# lp_pic32.net
KiCad netlist of a schematic drawn in EAGLE
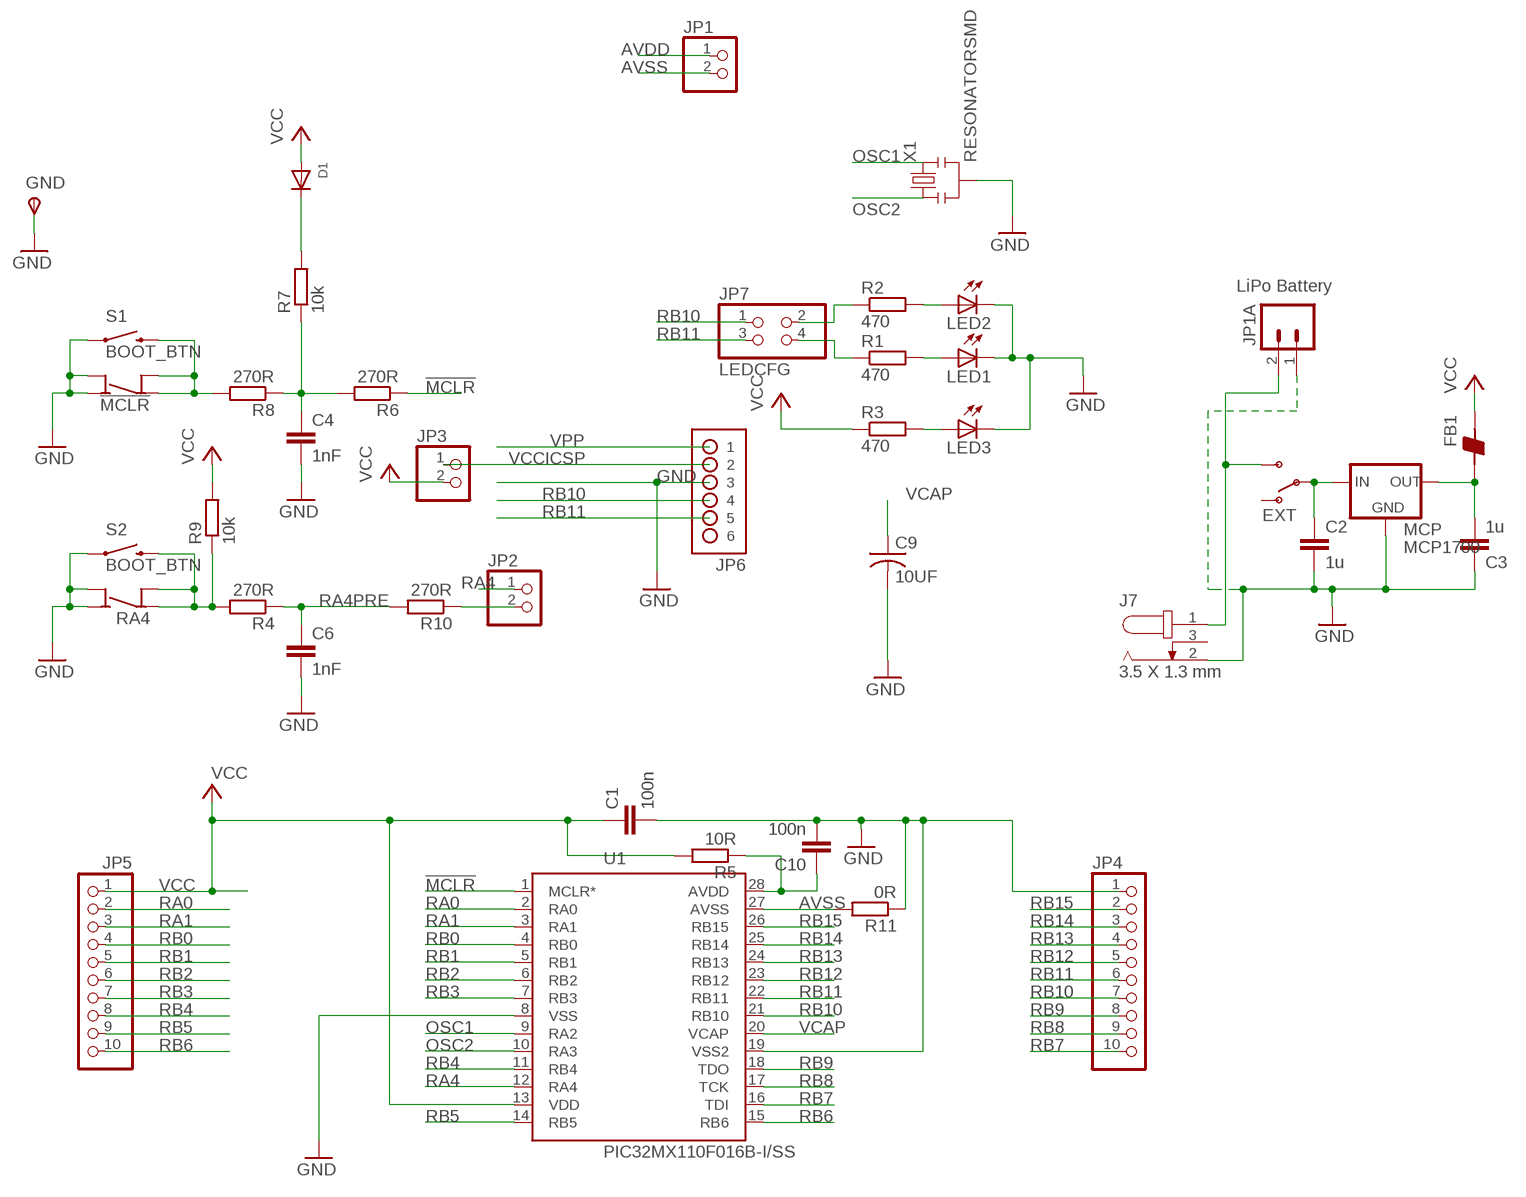
[diagram p0: schematic, sheet 1]

(export (version "E")
  (design (tool "Eeschema 10.0.6"))
  (components
    (comp (ref "!MCLR")
      (value "!MCLR")
      (footprint "eagle-import:6MMTACTILE_4PIN")
      (libsource (lib "eagle-import") (part "SPST4"))
    )
    (comp (ref "C1")
      (value "100n")
      (footprint "eagle-import:C0805")
      (libsource (lib "eagle-import") (part "C-EUC0805"))
    )
    (comp (ref "C2")
      (value "1u")
      (footprint "eagle-import:C0805")
      (libsource (lib "eagle-import") (part "C-EUC0805"))
    )
    (comp (ref "C3")
      (value "1u")
      (footprint "eagle-import:C0805")
      (libsource (lib "eagle-import") (part "C-EUC0805"))
    )
    (comp (ref "C4")
      (value "1nF")
      (footprint "eagle-import:C0805")
      (libsource (lib "eagle-import") (part "resistor_C-EUC0805"))
    )
    (comp (ref "C6")
      (value "1nF")
      (footprint "eagle-import:C0805")
      (libsource (lib "eagle-import") (part "resistor_C-EUC0805"))
    )
    (comp (ref "C9")
      (value "10UF")
      (footprint "eagle-import:C1206")
      (libsource (lib "eagle-import") (part "C-USC1206"))
    )
    (comp (ref "C10")
      (value "100n")
      (footprint "eagle-import:C0805")
      (libsource (lib "eagle-import") (part "C-EUC0805"))
    )
    (comp (ref "D1")
      (value "DIODESOD-323F")
      (footprint "eagle-import:SOD-323F")
      (libsource (lib "eagle-import") (part "DIODESOD-323F"))
    )
    (comp (ref "FB1")
      (value "BEAD-0805")
      (footprint "eagle-import:0805")
      (libsource (lib "eagle-import") (part "BEAD-0805"))
    )
    (comp (ref "GND")
      (value "TPSTP20R")
      (footprint "eagle-import:TP20R")
      (libsource (lib "eagle-import") (part "TPSTP20R"))
    )
    (comp (ref "J7")
      (value "3.5 X 1.3 mm")
      (footprint "eagle-import:3.5X1.3MM_DC_JACK")
      (libsource (lib "eagle-import") (part "DC_JACK_3.5X1.3MM"))
    )
    (comp (ref "JP1")
      (value "PINHD-1X2")
      (footprint "eagle-import:1X02")
      (libsource (lib "eagle-import") (part "PINHD-1X2"))
    )
    (comp (ref "JP1A")
      (value "LiPo Battery")
      (footprint "eagle-import:JST-2-PTH")
      (libsource (lib "eagle-import") (part "M02JST-PTH-2"))
    )
    (comp (ref "JP2")
      (value "PINHD-1X2")
      (footprint "eagle-import:1X02")
      (libsource (lib "eagle-import") (part "PINHD-1X2"))
    )
    (comp (ref "JP3")
      (value "PINHD-1X2")
      (footprint "eagle-import:1X02")
      (libsource (lib "eagle-import") (part "PINHD-1X2"))
    )
    (comp (ref "JP4")
      (value "PH1X10OCT076")
      (footprint "eagle-import:PH1X10OCT76")
      (libsource (lib "eagle-import") (part "PH1X10OCT076"))
    )
    (comp (ref "JP5")
      (value "PH1X10OCT076")
      (footprint "eagle-import:PH1X10OCT76")
      (libsource (lib "eagle-import") (part "PH1X10OCT076"))
    )
    (comp (ref "JP6")
      (value "No Load")
      (footprint "eagle-import:HDR-1X6_OFFSET")
      (libsource (lib "eagle-import") (part "HDR-1X6-OFFSET"))
    )
    (comp (ref "JP7")
      (value "LEDCFG")
      (footprint "eagle-import:2X02")
      (libsource (lib "eagle-import") (part "PINHD-2X2"))
    )
    (comp (ref "LED1")
      (value "0")
      (footprint "eagle-import:CHIPLED_1206")
      (libsource (lib "eagle-import") (part "LEDCHIPLED_1206"))
    )
    (comp (ref "LED2")
      (value "0")
      (footprint "eagle-import:CHIPLED_1206")
      (libsource (lib "eagle-import") (part "LEDCHIPLED_1206"))
    )
    (comp (ref "LED3")
      (value "0")
      (footprint "eagle-import:CHIPLED_1206")
      (libsource (lib "eagle-import") (part "LEDCHIPLED_1206"))
    )
    (comp (ref "MCP")
      (value "MCP1700")
      (footprint "eagle-import:SOT-23")
      (libsource (lib "eagle-import") (part "MCP1700SOT-23"))
    )
    (comp (ref "ON")
      (value "EXT")
      (footprint "eagle-import:SWITCH-SPDT")
      (libsource (lib "eagle-import") (part "SWITCH-SPSTPTH"))
    )
    (comp (ref "R1")
      (value "470")
      (footprint "eagle-import:R0805")
      (libsource (lib "eagle-import") (part "R-EU_R0805"))
    )
    (comp (ref "R2")
      (value "470")
      (footprint "eagle-import:R0805")
      (libsource (lib "eagle-import") (part "R-EU_R0805"))
    )
    (comp (ref "R3")
      (value "470")
      (footprint "eagle-import:R0805")
      (libsource (lib "eagle-import") (part "R-EU_R0805"))
    )
    (comp (ref "R4")
      (value "270R")
      (footprint "eagle-import:R0805")
      (libsource (lib "eagle-import") (part "R-EU_R0805"))
    )
    (comp (ref "R5")
      (value "10R")
      (footprint "eagle-import:R0805")
      (libsource (lib "eagle-import") (part "R-EU_R0805"))
    )
    (comp (ref "R6")
      (value "270R")
      (footprint "eagle-import:R0805")
      (libsource (lib "eagle-import") (part "R-EU_R0805"))
    )
    (comp (ref "R7")
      (value "10k")
      (footprint "eagle-import:R0805")
      (libsource (lib "eagle-import") (part "R-EU_R0805"))
    )
    (comp (ref "R8")
      (value "270R")
      (footprint "eagle-import:R0805")
      (libsource (lib "eagle-import") (part "R-EU_R0805"))
    )
    (comp (ref "R9")
      (value "10k")
      (footprint "eagle-import:R0805")
      (libsource (lib "eagle-import") (part "R-EU_R0805"))
    )
    (comp (ref "R10")
      (value "270R")
      (footprint "eagle-import:R0805")
      (libsource (lib "eagle-import") (part "R-EU_R0805"))
    )
    (comp (ref "R11")
      (value "0R")
      (footprint "eagle-import:R0805")
      (libsource (lib "eagle-import") (part "R-EU_R0805"))
    )
    (comp (ref "RA4")
      (value "RA4")
      (footprint "eagle-import:6MMTACTILE_4PIN")
      (libsource (lib "eagle-import") (part "SPST4"))
    )
    (comp (ref "S1")
      (value "BOOT_BTN")
      (footprint "eagle-import:TACTILE-SWITCH-1101NE")
      (libsource (lib "eagle-import") (part "SWITCH-MOMENTARY-2-SMD-1101NE"))
    )
    (comp (ref "S2")
      (value "BOOT_BTN")
      (footprint "eagle-import:TACTILE-SWITCH-1101NE")
      (libsource (lib "eagle-import") (part "SWITCH-MOMENTARY-2-SMD-1101NE"))
    )
    (comp (ref "U1")
      (value "PIC32MX110F016B-I/SS")
      (footprint "eagle-import:SOP65P780X200-28N")
      (libsource (lib "eagle-import") (part "PIC32MX/SS110F016B-I"))
    )
    (comp (ref "X1")
      (value "RESONATORSMD")
      (footprint "eagle-import:RESONATOR-SMD")
      (libsource (lib "eagle-import") (part "RESONATORSMD"))
    )
  )
  (nets
    (net (code "1") (name "/AVDD") (class "Default")
      (node (ref "C10") (pin "1") (pinfunction "1_1") (pintype "passive"))
      (node (ref "JP1") (pin "1") (pinfunction "1_1") (pintype "passive"))
      (node (ref "R5") (pin "1") (pinfunction "1_1") (pintype "passive"))
      (node (ref "U1") (pin "28") (pinfunction "AVDD_28") (pintype "power_in"))
    )
    (net (code "2") (name "/AVSS") (class "Default")
      (node (ref "JP1") (pin "2") (pinfunction "2_2") (pintype "passive"))
      (node (ref "R11") (pin "2") (pinfunction "2_2") (pintype "passive"))
      (node (ref "U1") (pin "27") (pinfunction "AVSS_27") (pintype "power_in"))
    )
    (net (code "3") (name "/OSC1") (class "Default")
      (node (ref "U1") (pin "9") (pinfunction "RA2_9") (pintype "bidirectional"))
      (node (ref "X1") (pin "3") (pinfunction "3_3") (pintype "passive"))
    )
    (net (code "4") (name "/OSC2") (class "Default")
      (node (ref "U1") (pin "10") (pinfunction "RA3_10") (pintype "bidirectional"))
      (node (ref "X1") (pin "1") (pinfunction "1_1") (pintype "passive"))
    )
    (net (code "5") (name "/RA0") (class "Default")
      (node (ref "JP5") (pin "2") (pinfunction "2_2") (pintype "passive"))
      (node (ref "U1") (pin "2") (pinfunction "RA0_2") (pintype "bidirectional"))
    )
    (net (code "6") (name "/RA1") (class "Default")
      (node (ref "JP5") (pin "3") (pinfunction "3_3") (pintype "passive"))
      (node (ref "U1") (pin "3") (pinfunction "RA1_3") (pintype "bidirectional"))
    )
    (net (code "7") (name "/RA4") (class "Default")
      (node (ref "JP2") (pin "1") (pinfunction "1_1") (pintype "passive"))
      (node (ref "U1") (pin "12") (pinfunction "RA4_12") (pintype "bidirectional"))
    )
    (net (code "8") (name "/RA4PRE") (class "Default")
      (node (ref "C6") (pin "1") (pinfunction "1_1") (pintype "passive"))
      (node (ref "R10") (pin "2") (pinfunction "2_2") (pintype "passive"))
      (node (ref "R4") (pin "1") (pinfunction "1_1") (pintype "passive"))
    )
    (net (code "9") (name "/RB0") (class "Default")
      (node (ref "JP5") (pin "4") (pinfunction "4_4") (pintype "passive"))
      (node (ref "U1") (pin "4") (pinfunction "RB0_4") (pintype "bidirectional"))
    )
    (net (code "10") (name "/RB1") (class "Default")
      (node (ref "JP5") (pin "5") (pinfunction "5_5") (pintype "passive"))
      (node (ref "U1") (pin "5") (pinfunction "RB1_5") (pintype "bidirectional"))
    )
    (net (code "11") (name "/RB2") (class "Default")
      (node (ref "JP5") (pin "6") (pinfunction "6_6") (pintype "passive"))
      (node (ref "U1") (pin "6") (pinfunction "RB2_6") (pintype "bidirectional"))
    )
    (net (code "12") (name "/RB3") (class "Default")
      (node (ref "JP5") (pin "7") (pinfunction "7_7") (pintype "passive"))
      (node (ref "U1") (pin "7") (pinfunction "RB3_7") (pintype "bidirectional"))
    )
    (net (code "13") (name "/RB4") (class "Default")
      (node (ref "JP5") (pin "8") (pinfunction "8_8") (pintype "passive"))
      (node (ref "U1") (pin "11") (pinfunction "RB4_11") (pintype "bidirectional"))
    )
    (net (code "14") (name "/RB5") (class "Default")
      (node (ref "JP5") (pin "9") (pinfunction "9_9") (pintype "passive"))
      (node (ref "U1") (pin "14") (pinfunction "RB5_14") (pintype "bidirectional"))
    )
    (net (code "15") (name "/RB6") (class "Default")
      (node (ref "JP5") (pin "10") (pinfunction "10_10") (pintype "passive"))
      (node (ref "U1") (pin "15") (pinfunction "RB6_15") (pintype "bidirectional"))
    )
    (net (code "16") (name "/RB7") (class "Default")
      (node (ref "JP4") (pin "10") (pinfunction "10_10") (pintype "passive"))
      (node (ref "U1") (pin "16") (pinfunction "TDI_16") (pintype "input"))
    )
    (net (code "17") (name "/RB8") (class "Default")
      (node (ref "JP4") (pin "9") (pinfunction "9_9") (pintype "passive"))
      (node (ref "U1") (pin "17") (pinfunction "TCK_17") (pintype "input"))
    )
    (net (code "18") (name "/RB9") (class "Default")
      (node (ref "JP4") (pin "8") (pinfunction "8_8") (pintype "passive"))
      (node (ref "U1") (pin "18") (pinfunction "TDO_18") (pintype "output"))
    )
    (net (code "19") (name "/RB10") (class "Default")
      (node (ref "JP4") (pin "7") (pinfunction "7_7") (pintype "passive"))
      (node (ref "JP6") (pin "4") (pinfunction "4_4") (pintype "passive"))
      (node (ref "JP7") (pin "1") (pinfunction "1_1") (pintype "passive"))
      (node (ref "U1") (pin "21") (pinfunction "RB10_21") (pintype "bidirectional"))
    )
    (net (code "20") (name "/RB11") (class "Default")
      (node (ref "JP4") (pin "6") (pinfunction "6_6") (pintype "passive"))
      (node (ref "JP6") (pin "5") (pinfunction "5_5") (pintype "passive"))
      (node (ref "JP7") (pin "3") (pinfunction "3_3") (pintype "passive"))
      (node (ref "U1") (pin "22") (pinfunction "RB11_22") (pintype "bidirectional"))
    )
    (net (code "21") (name "/RB12") (class "Default")
      (node (ref "JP4") (pin "5") (pinfunction "5_5") (pintype "passive"))
      (node (ref "U1") (pin "23") (pinfunction "RB12_23") (pintype "bidirectional"))
    )
    (net (code "22") (name "/RB13") (class "Default")
      (node (ref "JP4") (pin "4") (pinfunction "4_4") (pintype "passive"))
      (node (ref "U1") (pin "24") (pinfunction "RB13_24") (pintype "bidirectional"))
    )
    (net (code "23") (name "/RB14") (class "Default")
      (node (ref "JP4") (pin "3") (pinfunction "3_3") (pintype "passive"))
      (node (ref "U1") (pin "25") (pinfunction "RB14_25") (pintype "bidirectional"))
    )
    (net (code "24") (name "/RB15") (class "Default")
      (node (ref "JP4") (pin "2") (pinfunction "2_2") (pintype "passive"))
      (node (ref "U1") (pin "26") (pinfunction "RB15_26") (pintype "bidirectional"))
    )
    (net (code "25") (name "/VCAP") (class "Default")
      (node (ref "C9") (pin "1") (pinfunction "1_1") (pintype "passive"))
      (node (ref "U1") (pin "20") (pinfunction "VCAP_20") (pintype "power_in"))
    )
    (net (code "26") (name "/VCCICSP") (class "Default")
      (node (ref "JP3") (pin "1") (pinfunction "1_1") (pintype "passive"))
      (node (ref "JP6") (pin "2") (pinfunction "2_2") (pintype "passive"))
    )
    (net (code "27") (name "/VPP") (class "Default")
      (node (ref "C4") (pin "1") (pinfunction "1_1") (pintype "passive"))
      (node (ref "JP6") (pin "1") (pinfunction "1_1") (pintype "passive"))
      (node (ref "R6") (pin "2") (pinfunction "2_2") (pintype "passive"))
      (node (ref "R7") (pin "1") (pinfunction "1_1") (pintype "passive"))
      (node (ref "R8") (pin "1") (pinfunction "1_1") (pintype "passive"))
    )
    (net (code "28") (name "/~{MCLR}") (class "Default")
      (node (ref "R6") (pin "1") (pinfunction "1_1") (pintype "passive"))
      (node (ref "U1") (pin "1") (pinfunction "MCLR*_1") (pintype "input"))
    )
    (net (code "29") (name "GND") (class "Default")
      (node (ref "!MCLR") (pin "A1") (pinfunction "NO_A1") (pintype "passive"))
      (node (ref "!MCLR") (pin "A2") (pinfunction "NO_A2") (pintype "passive"))
      (node (ref "C1") (pin "2") (pinfunction "2_2") (pintype "passive"))
      (node (ref "C10") (pin "2") (pinfunction "2_2") (pintype "passive"))
      (node (ref "C2") (pin "2") (pinfunction "2_2") (pintype "passive"))
      (node (ref "C3") (pin "1") (pinfunction "1_1") (pintype "passive"))
      (node (ref "C4") (pin "2") (pinfunction "2_2") (pintype "passive"))
      (node (ref "C6") (pin "2") (pinfunction "2_2") (pintype "passive"))
      (node (ref "C9") (pin "2") (pinfunction "2_2") (pintype "passive"))
      (node (ref "GND") (pin "TP") (pinfunction "PP_TP") (pintype "input"))
      (node (ref "J7") (pin "2") (pinfunction "2_2") (pintype "passive"))
      (node (ref "JP1A") (pin "1") (pinfunction "1_1") (pintype "passive"))
      (node (ref "JP4") (pin "1") (pinfunction "1_1") (pintype "passive"))
      (node (ref "JP6") (pin "3") (pinfunction "3_3") (pintype "passive"))
      (node (ref "LED1") (pin "C") (pinfunction "C_C") (pintype "passive"))
      (node (ref "LED2") (pin "C") (pinfunction "C_C") (pintype "passive"))
      (node (ref "LED3") (pin "C") (pinfunction "C_C") (pintype "passive"))
      (node (ref "MCP") (pin "1") (pinfunction "GND_1") (pintype "input"))
      (node (ref "R11") (pin "1") (pinfunction "1_1") (pintype "passive"))
      (node (ref "RA4") (pin "A1") (pinfunction "NO_A1") (pintype "passive"))
      (node (ref "RA4") (pin "A2") (pinfunction "NO_A2") (pintype "passive"))
      (node (ref "S1") (pin "1") (pinfunction "1_1") (pintype "passive"))
      (node (ref "S2") (pin "1") (pinfunction "1_1") (pintype "passive"))
      (node (ref "U1") (pin "19") (pinfunction "VSS2_19") (pintype "power_in"))
      (node (ref "U1") (pin "8") (pinfunction "VSS_8") (pintype "power_in"))
      (node (ref "X1") (pin "2") (pinfunction "2_2") (pintype "passive"))
    )
    (net (code "30") (name "Net-(!MCLR-COM-PadB1)") (class "Default")
      (node (ref "!MCLR") (pin "B1") (pinfunction "COM_B1") (pintype "passive"))
      (node (ref "!MCLR") (pin "B2") (pinfunction "COM_B2") (pintype "passive"))
      (node (ref "R8") (pin "2") (pinfunction "2_2") (pintype "passive"))
      (node (ref "S1") (pin "2") (pinfunction "2_2") (pintype "passive"))
    )
    (net (code "31") (name "Net-(D1-PadC)") (class "Default")
      (node (ref "D1") (pin "C") (pinfunction "C_C") (pintype "passive"))
      (node (ref "R7") (pin "2") (pinfunction "2_2") (pintype "passive"))
    )
    (net (code "32") (name "Net-(FB1-P$1)") (class "Default")
      (node (ref "C3") (pin "2") (pinfunction "2_2") (pintype "passive"))
      (node (ref "FB1") (pin "1") (pinfunction "P$1_1") (pintype "passive"))
      (node (ref "MCP") (pin "2") (pinfunction "OUT_2") (pintype "passive"))
    )
    (net (code "33") (name "Net-(JP2-Pad2)") (class "Default")
      (node (ref "JP2") (pin "2") (pinfunction "2_2") (pintype "passive"))
      (node (ref "R10") (pin "1") (pinfunction "1_1") (pintype "passive"))
    )
    (net (code "34") (name "Net-(JP7-Pad2)") (class "Default")
      (node (ref "JP7") (pin "2") (pinfunction "2_2") (pintype "passive"))
      (node (ref "R2") (pin "1") (pinfunction "1_1") (pintype "passive"))
    )
    (net (code "35") (name "Net-(JP7-Pad4)") (class "Default")
      (node (ref "JP7") (pin "4") (pinfunction "4_4") (pintype "passive"))
      (node (ref "R1") (pin "1") (pinfunction "1_1") (pintype "passive"))
    )
    (net (code "36") (name "Net-(LED1-PadA)") (class "Default")
      (node (ref "LED1") (pin "A") (pinfunction "A_A") (pintype "passive"))
      (node (ref "R1") (pin "2") (pinfunction "2_2") (pintype "passive"))
    )
    (net (code "37") (name "Net-(LED2-PadA)") (class "Default")
      (node (ref "LED2") (pin "A") (pinfunction "A_A") (pintype "passive"))
      (node (ref "R2") (pin "2") (pinfunction "2_2") (pintype "passive"))
    )
    (net (code "38") (name "Net-(LED3-PadA)") (class "Default")
      (node (ref "LED3") (pin "A") (pinfunction "A_A") (pintype "passive"))
      (node (ref "R3") (pin "2") (pinfunction "2_2") (pintype "passive"))
    )
    (net (code "39") (name "Net-(MCP-IN)") (class "Default")
      (node (ref "C2") (pin "1") (pinfunction "1_1") (pintype "passive"))
      (node (ref "MCP") (pin "3") (pinfunction "IN_3") (pintype "input"))
      (node (ref "ON") (pin "2") (pinfunction "P_2") (pintype "passive"))
    )
    (net (code "40") (name "Net-(ON-S)") (class "Default")
      (node (ref "J7") (pin "1") (pinfunction "1_1") (pintype "passive"))
      (node (ref "JP1A") (pin "2") (pinfunction "2_2") (pintype "passive"))
      (node (ref "ON") (pin "3") (pinfunction "S_3") (pintype "passive"))
    )
    (net (code "41") (name "Net-(R4-Pad2)") (class "Default")
      (node (ref "R4") (pin "2") (pinfunction "2_2") (pintype "passive"))
      (node (ref "R9") (pin "1") (pinfunction "1_1") (pintype "passive"))
      (node (ref "RA4") (pin "B1") (pinfunction "COM_B1") (pintype "passive"))
      (node (ref "RA4") (pin "B2") (pinfunction "COM_B2") (pintype "passive"))
      (node (ref "S2") (pin "2") (pinfunction "2_2") (pintype "passive"))
    )
    (net (code "42") (name "VCC") (class "Default")
      (node (ref "C1") (pin "1") (pinfunction "1_1") (pintype "passive"))
      (node (ref "D1") (pin "A") (pinfunction "A_A") (pintype "passive"))
      (node (ref "FB1") (pin "2") (pinfunction "P$2_2") (pintype "passive"))
      (node (ref "JP3") (pin "2") (pinfunction "2_2") (pintype "passive"))
      (node (ref "JP5") (pin "1") (pinfunction "1_1") (pintype "passive"))
      (node (ref "R3") (pin "1") (pinfunction "1_1") (pintype "passive"))
      (node (ref "R5") (pin "2") (pinfunction "2_2") (pintype "passive"))
      (node (ref "R9") (pin "2") (pinfunction "2_2") (pintype "passive"))
      (node (ref "U1") (pin "13") (pinfunction "VDD_13") (pintype "power_in"))
    )
    (net (code "43") (name "unconnected-(J7-Pad3)") (class "Default")
      (node (ref "J7") (pin "3") (pinfunction "3_3") (pintype "passive"))
    )
    (net (code "44") (name "unconnected-(JP6-Pad6)") (class "Default")
      (node (ref "JP6") (pin "6") (pinfunction "6_6") (pintype "passive"))
    )
    (net (code "45") (name "unconnected-(ON-O-Pad1)") (class "Default")
      (node (ref "ON") (pin "1") (pinfunction "O_1") (pintype "passive"))
    )
  )
)
